# EasyEDA_file_SCH_Meshtastic_ESP32_RA01SH.net
KiCad netlist of a schematic drawn in EasyEDA
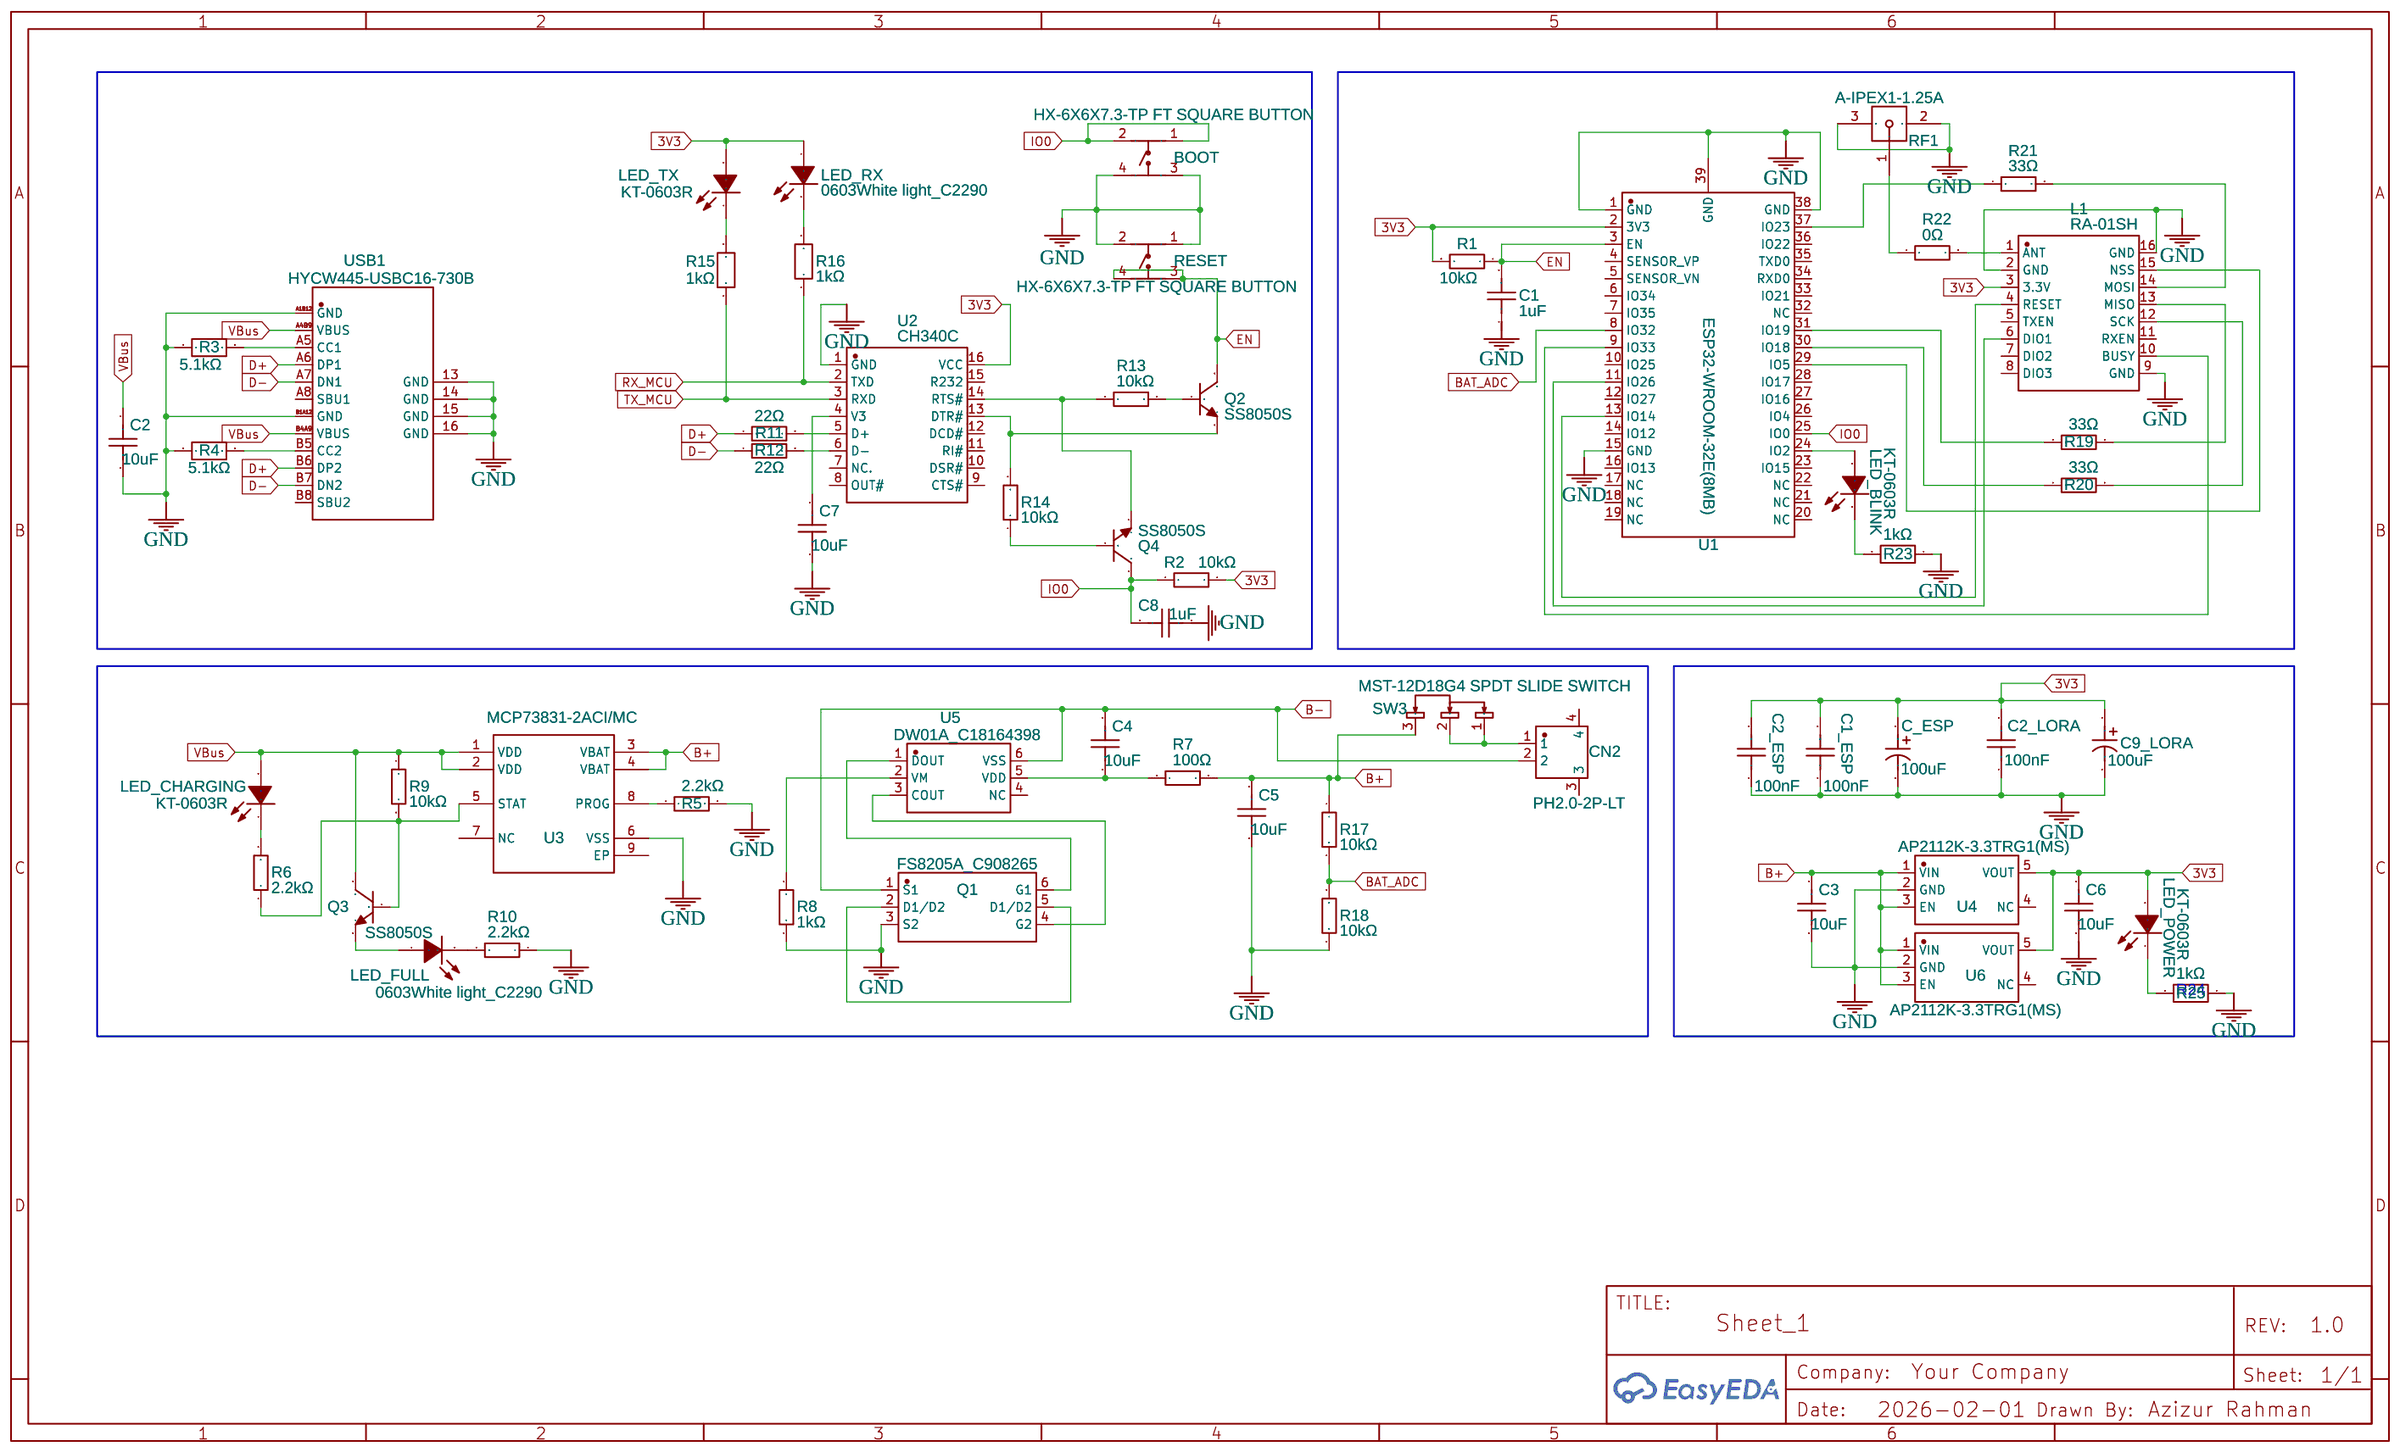
[diagram p0: schematic sheet]

(export (version "E")
  (design (tool "Eeschema 10.0.6"))
  (components
    (comp (ref "BOOT")
      (value "HX-6X6X7.3-TP FT SQUARE BUTTON")
      (fields
        (field (name "Manufacturer Part") "HX-6x6x7.3-TP FT square button")
        (field (name "Manufacturer") "hanxia(韩下)")
      )
      (libsource (lib "") (part "HX-6X6X7.3-TP FT SQUARE BUTTON_1"))
    )
    (comp (ref "C1")
      (value "1uF")
      (fields
        (field (name "Manufacturer Part") "CL10A105KB8NNNC")
        (field (name "Manufacturer") "SAMSUNG(三星)")
      )
      (libsource (lib "") (part "CL10A105KB8NNNC"))
    )
    (comp (ref "C1_ESP")
      (value "100nF")
      (fields
        (field (name "Manufacturer Part") "CL10B104KA8WPNC")
        (field (name "Manufacturer") "SAMSUNG(三星)")
      )
      (libsource (lib "") (part "CL10B104KA8WPNC_2"))
    )
    (comp (ref "C2")
      (value "10uF")
      (fields
        (field (name "Manufacturer Part") "CL10A106KP8NNNC")
        (field (name "Manufacturer") "SAMSUNG(三星)")
      )
      (libsource (lib "") (part "CL10A106KP8NNNC"))
    )
    (comp (ref "C2_ESP")
      (value "100nF")
      (fields
        (field (name "Manufacturer Part") "CL10B104KA8WPNC")
        (field (name "Manufacturer") "SAMSUNG(三星)")
      )
      (libsource (lib "") (part "CL10B104KA8WPNC"))
    )
    (comp (ref "C2_LORA")
      (value "100nF")
      (fields
        (field (name "Manufacturer Part") "CL10B104KA8WPNC")
        (field (name "Manufacturer") "SAMSUNG(三星)")
      )
      (libsource (lib "") (part "CL10B104KA8WPNC_1"))
    )
    (comp (ref "C3")
      (value "10uF")
      (fields
        (field (name "Manufacturer Part") "CL10A106KP8NNNC")
        (field (name "Manufacturer") "SAMSUNG(三星)")
      )
      (libsource (lib "") (part "CL10A106KP8NNNC"))
    )
    (comp (ref "C4")
      (value "10uF")
      (fields
        (field (name "Manufacturer Part") "CL10A106KP8NNNC")
        (field (name "Manufacturer") "SAMSUNG(三星)")
      )
      (libsource (lib "") (part "CL10A106KP8NNNC"))
    )
    (comp (ref "C5")
      (value "10uF")
      (fields
        (field (name "Manufacturer Part") "CL10A106KP8NNNC")
        (field (name "Manufacturer") "SAMSUNG(三星)")
      )
      (libsource (lib "") (part "CL10A106KP8NNNC"))
    )
    (comp (ref "C6")
      (value "10uF")
      (fields
        (field (name "Manufacturer Part") "CL10A106KP8NNNC")
        (field (name "Manufacturer") "SAMSUNG(三星)")
      )
      (libsource (lib "") (part "CL10A106KP8NNNC"))
    )
    (comp (ref "C7")
      (value "10uF")
      (fields
        (field (name "Manufacturer Part") "CL10A106KP8NNNC")
        (field (name "Manufacturer") "SAMSUNG(三星)")
      )
      (libsource (lib "") (part "CL10A106KP8NNNC"))
    )
    (comp (ref "C8")
      (value "1uF")
      (fields
        (field (name "Manufacturer Part") "CL10A105KB8NNNC")
        (field (name "Manufacturer") "SAMSUNG(三星)")
      )
      (libsource (lib "") (part "CL10A105KB8NNNC_1"))
    )
    (comp (ref "C9_LORA")
      (value "100uF")
      (fields
        (field (name "Manufacturer Part") "RVT100UF16V67RV0120")
        (field (name "Manufacturer") "KNSCHA(科尼盛)")
      )
      (libsource (lib "") (part "RVT100UF16V67RV0120_1"))
    )
    (comp (ref "CN2")
      (value "PH2.0-2P-LT")
      (fields (field (name "Manufacturer") "CAX(创都)"))
      (libsource (lib "") (part "PH2.0-2P-LT"))
    )
    (comp (ref "C_ESP")
      (value "100uF")
      (fields
        (field (name "Manufacturer Part") "RVT100UF16V67RV0120")
        (field (name "Manufacturer") "KNSCHA(科尼盛)")
      )
      (libsource (lib "") (part "RVT100UF16V67RV0120"))
    )
    (comp (ref "L1")
      (value "RA-01SH")
      (fields (field (name "Manufacturer Part") "Ra-01SH") (field (name "Manufacturer") "Ai-Thinker(安信可)"))
      (libsource (lib "") (part "RA-01SH"))
    )
    (comp (ref "LED_BLINK")
      (value "KT-0603R")
      (fields (field (name "Manufacturer") "KENTO"))
      (libsource (lib "") (part "KT-0603R_2"))
    )
    (comp (ref "LED_CHARGING")
      (value "KT-0603R")
      (fields (field (name "Manufacturer") "KENTO"))
      (libsource (lib "") (part "KT-0603R_1"))
    )
    (comp (ref "LED_FULL")
      (value "0603White light_C2290")
      (fields (field (name "Manufacturer Part") "KT-0603W") (field (name "Manufacturer") "KENTO"))
      (libsource (lib "") (part "0603White light_C2290_1"))
    )
    (comp (ref "LED_POWER")
      (value "KT-0603R")
      (fields (field (name "Manufacturer") "KENTO"))
      (libsource (lib "") (part "KT-0603R"))
    )
    (comp (ref "LED_RX")
      (value "0603White light_C2290")
      (fields (field (name "Manufacturer Part") "KT-0603W") (field (name "Manufacturer") "KENTO"))
      (libsource (lib "") (part "0603White light_C2290"))
    )
    (comp (ref "LED_TX")
      (value "KT-0603R")
      (fields (field (name "Manufacturer") "KENTO"))
      (libsource (lib "") (part "KT-0603R_3"))
    )
    (comp (ref "Q1")
      (value "FS8205A_C908265")
      (fields (field (name "Manufacturer Part") "FS8205A") (field (name "Manufacturer") "FUXINSEMI(富芯森美)"))
      (libsource (lib "") (part "FS8205A_C908265"))
    )
    (comp (ref "Q2")
      (value "SS8050S")
      (fields (field (name "Manufacturer") "FOSAN(富捷/富信)"))
      (libsource (lib "") (part "SS8050S_2"))
    )
    (comp (ref "Q3")
      (value "SS8050S")
      (fields (field (name "Manufacturer") "FOSAN(富捷/富信)"))
      (libsource (lib "") (part "SS8050S"))
    )
    (comp (ref "Q4")
      (value "SS8050S")
      (fields (field (name "Manufacturer") "FOSAN(富捷/富信)"))
      (libsource (lib "") (part "SS8050S_1"))
    )
    (comp (ref "R1")
      (value "10kΩ")
      (fields
        (field (name "Manufacturer Part") "0603WAF1002T5E")
        (field (name "Manufacturer") "UNI-ROYAL(厚声)")
      )
      (libsource (lib "") (part "0603WAF1002T5E_1"))
    )
    (comp (ref "R2")
      (value "10kΩ")
      (fields
        (field (name "Manufacturer Part") "0603WAF1002T5E")
        (field (name "Manufacturer") "UNI-ROYAL(厚声)")
      )
      (libsource (lib "") (part "0603WAF1002T5E_1"))
    )
    (comp (ref "R3")
      (value "5.1kΩ")
      (fields (field (name "Manufacturer Part") "SCR0603F5K1") (field (name "Manufacturer") "VO(翔胜)"))
      (libsource (lib "") (part "SCR0603F5K1"))
    )
    (comp (ref "R4")
      (value "5.1kΩ")
      (fields (field (name "Manufacturer Part") "SCR0603F5K1") (field (name "Manufacturer") "VO(翔胜)"))
      (libsource (lib "") (part "SCR0603F5K1"))
    )
    (comp (ref "R5")
      (value "2.2kΩ")
      (fields
        (field (name "Manufacturer Part") "0603WAF2201T5E")
        (field (name "Manufacturer") "UNI-ROYAL(厚声)")
      )
      (libsource (lib "") (part "0603WAF2201T5E"))
    )
    (comp (ref "R6")
      (value "2.2kΩ")
      (fields
        (field (name "Manufacturer Part") "0603WAF2201T5E")
        (field (name "Manufacturer") "UNI-ROYAL(厚声)")
      )
      (libsource (lib "") (part "0603WAF2201T5E_2"))
    )
    (comp (ref "R7")
      (value "100Ω")
      (fields
        (field (name "Manufacturer Part") "0603WAF1000T5E")
        (field (name "Manufacturer") "UNI-ROYAL(厚声)")
      )
      (libsource (lib "") (part "0603WAF1000T5E"))
    )
    (comp (ref "R8")
      (value "1kΩ")
      (fields
        (field (name "Manufacturer Part") "0603WAF1001T5E")
        (field (name "Manufacturer") "UNI-ROYAL(厚声)")
      )
      (libsource (lib "") (part "0603WAF1001T5E"))
    )
    (comp (ref "R9")
      (value "10kΩ")
      (fields
        (field (name "Manufacturer Part") "0603WAF1002T5E")
        (field (name "Manufacturer") "UNI-ROYAL(厚声)")
      )
      (libsource (lib "") (part "0603WAF1002T5E"))
    )
    (comp (ref "R10")
      (value "2.2kΩ")
      (fields
        (field (name "Manufacturer Part") "0603WAF2201T5E")
        (field (name "Manufacturer") "UNI-ROYAL(厚声)")
      )
      (libsource (lib "") (part "0603WAF2201T5E_1"))
    )
    (comp (ref "R11")
      (value "22Ω")
      (fields (field (name "Manufacturer Part") "CR1206J40220G") (field (name "Manufacturer") "LIZ(丽智电子)"))
      (libsource (lib "") (part "CR1206J40220G"))
    )
    (comp (ref "R12")
      (value "22Ω")
      (fields (field (name "Manufacturer Part") "CR1206J40220G") (field (name "Manufacturer") "LIZ(丽智电子)"))
      (libsource (lib "") (part "CR1206J40220G"))
    )
    (comp (ref "R13")
      (value "10kΩ")
      (fields
        (field (name "Manufacturer Part") "0603WAF1002T5E")
        (field (name "Manufacturer") "UNI-ROYAL(厚声)")
      )
      (libsource (lib "") (part "0603WAF1002T5E_2"))
    )
    (comp (ref "R14")
      (value "10kΩ")
      (fields
        (field (name "Manufacturer Part") "0603WAF1002T5E")
        (field (name "Manufacturer") "UNI-ROYAL(厚声)")
      )
      (libsource (lib "") (part "0603WAF1002T5E_3"))
    )
    (comp (ref "R15")
      (value "1kΩ")
      (fields (field (name "Manufacturer Part") "FRC1206J102 TS") (field (name "Manufacturer") "FOJAN(富捷)"))
      (libsource (lib "") (part "FRC1206J102 TS_1"))
    )
    (comp (ref "R16")
      (value "1kΩ")
      (fields (field (name "Manufacturer Part") "FRC1206J102 TS") (field (name "Manufacturer") "FOJAN(富捷)"))
      (libsource (lib "") (part "FRC1206J102 TS_1"))
    )
    (comp (ref "R17")
      (value "10kΩ")
      (fields
        (field (name "Manufacturer Part") "0603WAF1002T5E")
        (field (name "Manufacturer") "UNI-ROYAL(厚声)")
      )
      (libsource (lib "") (part "0603WAF1002T5E"))
    )
    (comp (ref "R18")
      (value "10kΩ")
      (fields
        (field (name "Manufacturer Part") "0603WAF1002T5E")
        (field (name "Manufacturer") "UNI-ROYAL(厚声)")
      )
      (libsource (lib "") (part "0603WAF1002T5E"))
    )
    (comp (ref "R19")
      (value "33Ω")
      (fields
        (field (name "Manufacturer Part") "0603WAF330JT5E")
        (field (name "Manufacturer") "UNI-ROYAL(厚声)")
      )
      (libsource (lib "") (part "0603WAF330JT5E"))
    )
    (comp (ref "R20")
      (value "33Ω")
      (fields
        (field (name "Manufacturer Part") "0603WAF330JT5E")
        (field (name "Manufacturer") "UNI-ROYAL(厚声)")
      )
      (libsource (lib "") (part "0603WAF330JT5E"))
    )
    (comp (ref "R21")
      (value "33Ω")
      (fields
        (field (name "Manufacturer Part") "0603WAF330JT5E")
        (field (name "Manufacturer") "UNI-ROYAL(厚声)")
      )
      (libsource (lib "") (part "0603WAF330JT5E"))
    )
    (comp (ref "R22")
      (value "0Ω")
      (fields
        (field (name "Manufacturer Part") "0805W8J0000T5E")
        (field (name "Manufacturer") "UNI-ROYAL(厚声)")
      )
      (libsource (lib "") (part "0805W8J0000T5E"))
    )
    (comp (ref "R23")
      (value "1kΩ")
      (fields (field (name "Manufacturer Part") "FRC1206J102 TS") (field (name "Manufacturer") "FOJAN(富捷)"))
      (libsource (lib "") (part "FRC1206J102 TS"))
    )
    (comp (ref "R25")
      (value "1kΩ")
      (fields (field (name "Manufacturer Part") "FRC1206J102 TS") (field (name "Manufacturer") "FOJAN(富捷)"))
      (libsource (lib "") (part "FRC1206J102 TS"))
    )
    (comp (ref "RESET")
      (value "HX-6X6X7.3-TP FT SQUARE BUTTON")
      (fields
        (field (name "Manufacturer Part") "HX-6x6x7.3-TP FT square button")
        (field (name "Manufacturer") "hanxia(韩下)")
      )
      (libsource (lib "") (part "HX-6X6X7.3-TP FT SQUARE BUTTON"))
    )
    (comp (ref "RF1")
      (value "A-IPEX1-1.25A")
      (fields (field (name "Manufacturer") "MyAntenna(摩天射频)"))
      (libsource (lib "") (part "A-IPEX1-1.25A"))
    )
    (comp (ref "SW3")
      (value "MST-12D18G4 SPDT SLIDE SWITCH")
      (fields
        (field (name "Manufacturer Part") "MST-12D18G4 SPDT Slide Switch")
        (field (name "Manufacturer") "SHOU HAN(首韩)")
      )
      (libsource (lib "") (part "MST-12D18G4 SPDT SLIDE SWITCH"))
    )
    (comp (ref "U1")
      (value "ESP32-WROOM-32E(8MB)")
      (fields
        (field (name "Manufacturer Part") "ESP32-WROOM-32E-N8")
        (field (name "Manufacturer") "ESPRESSIF(乐鑫)")
      )
      (libsource (lib "") (part "ESP32-WROOM-32E(8MB)"))
    )
    (comp (ref "U2")
      (value "CH340C")
      (fields (field (name "Manufacturer") "WCH(南京沁恒)"))
      (libsource (lib "") (part "CH340C"))
    )
    (comp (ref "U3")
      (value "MCP73831-2ACI/MC")
      (fields (field (name "Manufacturer") "MICROCHIP(美国微芯)"))
      (libsource (lib "") (part "MCP73831-2ACI/MC"))
    )
    (comp (ref "U4")
      (value "AP2112K-3.3TRG1(MS)")
      (fields (field (name "Manufacturer") "MSKSEMI(美森科)"))
      (libsource (lib "") (part "AP2112K-3.3TRG1(MS)"))
    )
    (comp (ref "U5")
      (value "DW01A_C18164398")
      (fields (field (name "Manufacturer Part") "DW01A") (field (name "Manufacturer") "HL(富海微)"))
      (libsource (lib "") (part "DW01A_C18164398"))
    )
    (comp (ref "U6")
      (value "AP2112K-3.3TRG1(MS)")
      (fields (field (name "Manufacturer") "MSKSEMI(美森科)"))
      (libsource (lib "") (part "AP2112K-3.3TRG1(MS)"))
    )
    (comp (ref "USB1")
      (value "HYCW445-USBC16-730B")
      (fields (field (name "Manufacturer") "华宇创"))
      (libsource (lib "") (part "HYCW445-USBC16-730B"))
    )
  )
  (nets
    (net (code "1") (name "3V3") (class "Default")
      (node (ref "C1_ESP") (pin "2") (pinfunction "2_2") (pintype "unspecified"))
      (node (ref "C2_ESP") (pin "2") (pinfunction "2_2") (pintype "unspecified"))
      (node (ref "C2_LORA") (pin "2") (pinfunction "2_2") (pintype "unspecified"))
      (node (ref "C6") (pin "1") (pinfunction "1_1") (pintype "unspecified"))
      (node (ref "C9_LORA") (pin "1") (pinfunction "1_1") (pintype "input"))
      (node (ref "C_ESP") (pin "1") (pinfunction "1_1") (pintype "input"))
      (node (ref "L1") (pin "3") (pinfunction "3.3V_3") (pintype "unspecified"))
      (node (ref "LED_POWER") (pin "2") (pinfunction "A_2") (pintype "unspecified"))
      (node (ref "LED_RX") (pin "1") (pinfunction "A_1") (pintype "unspecified"))
      (node (ref "LED_TX") (pin "2") (pinfunction "A_2") (pintype "unspecified"))
      (node (ref "R1") (pin "2") (pinfunction "2_2") (pintype "input"))
      (node (ref "R2") (pin "1") (pinfunction "1_1") (pintype "input"))
      (node (ref "U1") (pin "2") (pinfunction "3V3_2") (pintype "unspecified"))
      (node (ref "U2") (pin "16") (pinfunction "VCC_16") (pintype "unspecified"))
      (node (ref "U4") (pin "5") (pinfunction "VOUT_5") (pintype "unspecified"))
      (node (ref "U6") (pin "5") (pinfunction "VOUT_5") (pintype "unspecified"))
    )
    (net (code "2") (name "B+") (class "Default")
      (node (ref "C3") (pin "1") (pinfunction "1_1") (pintype "unspecified"))
      (node (ref "C5") (pin "1") (pinfunction "1_1") (pintype "unspecified"))
      (node (ref "R17") (pin "1") (pinfunction "1_1") (pintype "input"))
      (node (ref "R7") (pin "2") (pinfunction "2_2") (pintype "input"))
      (node (ref "SW3") (pin "3") (pinfunction "3_3") (pintype "unspecified"))
      (node (ref "U3") (pin "3") (pinfunction "VBAT_3") (pintype "passive"))
      (node (ref "U3") (pin "4") (pinfunction "VBAT_4") (pintype "passive"))
      (node (ref "U4") (pin "1") (pinfunction "VIN_1") (pintype "unspecified"))
      (node (ref "U4") (pin "3") (pinfunction "EN_3") (pintype "unspecified"))
      (node (ref "U6") (pin "1") (pinfunction "VIN_1") (pintype "unspecified"))
      (node (ref "U6") (pin "3") (pinfunction "EN_3") (pintype "unspecified"))
    )
    (net (code "3") (name "B-") (class "Default")
      (node (ref "C4") (pin "1") (pinfunction "1_1") (pintype "unspecified"))
      (node (ref "CN2") (pin "2") (pinfunction "2_2") (pintype "unspecified"))
      (node (ref "Q1") (pin "1") (pinfunction "S1_1") (pintype "unspecified"))
      (node (ref "U5") (pin "6") (pinfunction "VSS_6") (pintype "unspecified"))
    )
    (net (code "4") (name "BAT_ADC") (class "Default")
      (node (ref "R17") (pin "2") (pinfunction "2_2") (pintype "input"))
      (node (ref "R18") (pin "1") (pinfunction "1_1") (pintype "input"))
      (node (ref "U1") (pin "8") (pinfunction "IO32_8") (pintype "unspecified"))
    )
    (net (code "5") (name "D+") (class "Default")
      (node (ref "R11") (pin "1") (pinfunction "1_1") (pintype "input"))
      (node (ref "USB1") (pin "A6") (pinfunction "DP1_A6") (pintype "unspecified"))
      (node (ref "USB1") (pin "B6") (pinfunction "DP2_B6") (pintype "unspecified"))
    )
    (net (code "6") (name "D-") (class "Default")
      (node (ref "R12") (pin "1") (pinfunction "1_1") (pintype "input"))
      (node (ref "USB1") (pin "A7") (pinfunction "DN1_A7") (pintype "unspecified"))
      (node (ref "USB1") (pin "B7") (pinfunction "DN2_B7") (pintype "unspecified"))
    )
    (net (code "7") (name "EN") (class "Default")
      (node (ref "C1") (pin "2") (pinfunction "2_2") (pintype "unspecified"))
      (node (ref "Q2") (pin "3") (pinfunction "C_3") (pintype "input"))
      (node (ref "R1") (pin "1") (pinfunction "1_1") (pintype "input"))
      (node (ref "RESET") (pin "3") (pinfunction "C_3") (pintype "unspecified"))
      (node (ref "RESET") (pin "4") (pinfunction "D_4") (pintype "unspecified"))
      (node (ref "U1") (pin "3") (pinfunction "EN_3") (pintype "unspecified"))
    )
    (net (code "8") (name "GND") (class "Default")
      (node (ref "BOOT") (pin "3") (pinfunction "C_3") (pintype "unspecified"))
      (node (ref "BOOT") (pin "4") (pinfunction "D_4") (pintype "unspecified"))
      (node (ref "C1") (pin "1") (pinfunction "1_1") (pintype "unspecified"))
      (node (ref "C1_ESP") (pin "1") (pinfunction "1_1") (pintype "unspecified"))
      (node (ref "C2") (pin "2") (pinfunction "2_2") (pintype "unspecified"))
      (node (ref "C2_ESP") (pin "1") (pinfunction "1_1") (pintype "unspecified"))
      (node (ref "C2_LORA") (pin "1") (pinfunction "1_1") (pintype "unspecified"))
      (node (ref "C3") (pin "2") (pinfunction "2_2") (pintype "unspecified"))
      (node (ref "C5") (pin "2") (pinfunction "2_2") (pintype "unspecified"))
      (node (ref "C6") (pin "2") (pinfunction "2_2") (pintype "unspecified"))
      (node (ref "C7") (pin "2") (pinfunction "2_2") (pintype "unspecified"))
      (node (ref "C8") (pin "1") (pinfunction "1_1") (pintype "unspecified"))
      (node (ref "C9_LORA") (pin "2") (pinfunction "2_2") (pintype "input"))
      (node (ref "C_ESP") (pin "2") (pinfunction "2_2") (pintype "input"))
      (node (ref "L1") (pin "16") (pinfunction "GND_16") (pintype "unspecified"))
      (node (ref "L1") (pin "2") (pinfunction "GND_2") (pintype "unspecified"))
      (node (ref "L1") (pin "9") (pinfunction "GND_9") (pintype "unspecified"))
      (node (ref "Q1") (pin "3") (pinfunction "S2_3") (pintype "unspecified"))
      (node (ref "R10") (pin "1") (pinfunction "1_1") (pintype "input"))
      (node (ref "R18") (pin "2") (pinfunction "2_2") (pintype "input"))
      (node (ref "R23") (pin "1") (pinfunction "1_1") (pintype "unspecified"))
      (node (ref "R25") (pin "1") (pinfunction "1_1") (pintype "unspecified"))
      (node (ref "R3") (pin "1") (pinfunction "1_1") (pintype "unspecified"))
      (node (ref "R4") (pin "1") (pinfunction "1_1") (pintype "unspecified"))
      (node (ref "R5") (pin "2") (pinfunction "2_2") (pintype "input"))
      (node (ref "R8") (pin "2") (pinfunction "2_2") (pintype "input"))
      (node (ref "RESET") (pin "1") (pinfunction "A_1") (pintype "unspecified"))
      (node (ref "RESET") (pin "2") (pinfunction "B_2") (pintype "unspecified"))
      (node (ref "RF1") (pin "2") (pinfunction "2_2") (pintype "unspecified"))
      (node (ref "RF1") (pin "3") (pinfunction "3_3") (pintype "unspecified"))
      (node (ref "U1") (pin "1") (pinfunction "GND_1") (pintype "unspecified"))
      (node (ref "U1") (pin "15") (pinfunction "GND_15") (pintype "unspecified"))
      (node (ref "U1") (pin "38") (pinfunction "GND_38") (pintype "unspecified"))
      (node (ref "U1") (pin "39") (pinfunction "GND_39") (pintype "unspecified"))
      (node (ref "U2") (pin "1") (pinfunction "GND_1") (pintype "unspecified"))
      (node (ref "U3") (pin "6") (pinfunction "VSS_6") (pintype "passive"))
      (node (ref "U4") (pin "2") (pinfunction "GND_2") (pintype "unspecified"))
      (node (ref "U6") (pin "2") (pinfunction "GND_2") (pintype "unspecified"))
      (node (ref "USB1") (pin "13") (pinfunction "GND_13") (pintype "unspecified"))
      (node (ref "USB1") (pin "14") (pinfunction "GND_14") (pintype "unspecified"))
      (node (ref "USB1") (pin "15") (pinfunction "GND_15") (pintype "unspecified"))
      (node (ref "USB1") (pin "16") (pinfunction "GND_16") (pintype "unspecified"))
      (node (ref "USB1") (pin "A1B12") (pinfunction "GND_A1B12") (pintype "unspecified"))
      (node (ref "USB1") (pin "B1A12") (pinfunction "GND_B1A12") (pintype "unspecified"))
    )
    (net (code "9") (name "IO0") (class "Default")
      (node (ref "BOOT") (pin "1") (pinfunction "A_1") (pintype "unspecified"))
      (node (ref "BOOT") (pin "2") (pinfunction "B_2") (pintype "unspecified"))
      (node (ref "C8") (pin "2") (pinfunction "2_2") (pintype "unspecified"))
      (node (ref "Q4") (pin "3") (pinfunction "C_3") (pintype "input"))
      (node (ref "R2") (pin "2") (pinfunction "2_2") (pintype "input"))
      (node (ref "U1") (pin "25") (pinfunction "IO0_25") (pintype "unspecified"))
    )
    (net (code "10") (name "Net-(CN2-Pad1)") (class "Default")
      (node (ref "CN2") (pin "1") (pinfunction "1_1") (pintype "unspecified"))
      (node (ref "SW3") (pin "1") (pinfunction "1_1") (pintype "unspecified"))
      (node (ref "SW3") (pin "2") (pinfunction "2_2") (pintype "unspecified"))
    )
    (net (code "11") (name "Net-(L1-ANT)") (class "Default")
      (node (ref "L1") (pin "1") (pinfunction "ANT_1") (pintype "unspecified"))
      (node (ref "R22") (pin "2") (pinfunction "2_2") (pintype "input"))
    )
    (net (code "12") (name "Net-(L1-BUSY)") (class "Default")
      (node (ref "L1") (pin "10") (pinfunction "BUSY_10") (pintype "unspecified"))
      (node (ref "U1") (pin "9") (pinfunction "IO33_9") (pintype "unspecified"))
    )
    (net (code "13") (name "Net-(L1-DIO1)") (class "Default")
      (node (ref "L1") (pin "6") (pinfunction "DIO1_6") (pintype "unspecified"))
      (node (ref "U1") (pin "11") (pinfunction "IO26_11") (pintype "unspecified"))
    )
    (net (code "14") (name "Net-(L1-MISO)") (class "Default")
      (node (ref "L1") (pin "13") (pinfunction "MISO_13") (pintype "unspecified"))
      (node (ref "R19") (pin "2") (pinfunction "2_2") (pintype "input"))
    )
    (net (code "15") (name "Net-(L1-MOSI)") (class "Default")
      (node (ref "L1") (pin "14") (pinfunction "MOSI_14") (pintype "unspecified"))
      (node (ref "R21") (pin "2") (pinfunction "2_2") (pintype "input"))
    )
    (net (code "16") (name "Net-(L1-NSS)") (class "Default")
      (node (ref "L1") (pin "15") (pinfunction "NSS_15") (pintype "unspecified"))
      (node (ref "U1") (pin "29") (pinfunction "IO5_29") (pintype "unspecified"))
    )
    (net (code "17") (name "Net-(L1-RESET)") (class "Default")
      (node (ref "L1") (pin "4") (pinfunction "RESET_4") (pintype "unspecified"))
      (node (ref "U1") (pin "13") (pinfunction "IO14_13") (pintype "unspecified"))
    )
    (net (code "18") (name "Net-(L1-SCK)") (class "Default")
      (node (ref "L1") (pin "12") (pinfunction "SCK_12") (pintype "unspecified"))
      (node (ref "R20") (pin "2") (pinfunction "2_2") (pintype "input"))
    )
    (net (code "19") (name "Net-(LED_BLINK-A)") (class "Default")
      (node (ref "LED_BLINK") (pin "2") (pinfunction "A_2") (pintype "unspecified"))
      (node (ref "U1") (pin "24") (pinfunction "IO2_24") (pintype "unspecified"))
    )
    (net (code "20") (name "Net-(LED_BLINK-K)") (class "Default")
      (node (ref "LED_BLINK") (pin "1") (pinfunction "K_1") (pintype "unspecified"))
      (node (ref "R23") (pin "2") (pinfunction "2_2") (pintype "unspecified"))
    )
    (net (code "21") (name "Net-(LED_CHARGING-K)") (class "Default")
      (node (ref "LED_CHARGING") (pin "1") (pinfunction "K_1") (pintype "unspecified"))
      (node (ref "R6") (pin "2") (pinfunction "2_2") (pintype "input"))
    )
    (net (code "22") (name "Net-(LED_FULL-A)") (class "Default")
      (node (ref "LED_FULL") (pin "1") (pinfunction "A_1") (pintype "unspecified"))
      (node (ref "Q3") (pin "2") (pinfunction "E_2") (pintype "input"))
    )
    (net (code "23") (name "Net-(LED_FULL-K)") (class "Default")
      (node (ref "LED_FULL") (pin "2") (pinfunction "K_2") (pintype "unspecified"))
      (node (ref "R10") (pin "2") (pinfunction "2_2") (pintype "input"))
    )
    (net (code "24") (name "Net-(LED_POWER-K)") (class "Default")
      (node (ref "LED_POWER") (pin "1") (pinfunction "K_1") (pintype "unspecified"))
      (node (ref "R25") (pin "2") (pinfunction "2_2") (pintype "unspecified"))
    )
    (net (code "25") (name "Net-(LED_RX-K)") (class "Default")
      (node (ref "LED_RX") (pin "2") (pinfunction "K_2") (pintype "unspecified"))
      (node (ref "R16") (pin "2") (pinfunction "2_2") (pintype "unspecified"))
    )
    (net (code "26") (name "Net-(LED_TX-K)") (class "Default")
      (node (ref "LED_TX") (pin "1") (pinfunction "K_1") (pintype "unspecified"))
      (node (ref "R15") (pin "2") (pinfunction "2_2") (pintype "unspecified"))
    )
    (net (code "27") (name "Net-(Q1-D1{slash}D2-Pad2)") (class "Default")
      (node (ref "Q1") (pin "2") (pinfunction "D1/D2_2") (pintype "unspecified"))
      (node (ref "Q1") (pin "5") (pinfunction "D1/D2_5") (pintype "unspecified"))
    )
    (net (code "28") (name "Net-(Q1-G1)") (class "Default")
      (node (ref "Q1") (pin "6") (pinfunction "G1_6") (pintype "unspecified"))
      (node (ref "U5") (pin "1") (pinfunction "DOUT_1") (pintype "unspecified"))
    )
    (net (code "29") (name "Net-(Q1-G2)") (class "Default")
      (node (ref "Q1") (pin "4") (pinfunction "G2_4") (pintype "unspecified"))
      (node (ref "U5") (pin "3") (pinfunction "COUT_3") (pintype "unspecified"))
    )
    (net (code "30") (name "Net-(Q2-B)") (class "Default")
      (node (ref "Q2") (pin "1") (pinfunction "B_1") (pintype "input"))
      (node (ref "R13") (pin "2") (pinfunction "2_2") (pintype "input"))
    )
    (net (code "31") (name "Net-(Q2-E)") (class "Default")
      (node (ref "Q2") (pin "2") (pinfunction "E_2") (pintype "input"))
      (node (ref "R14") (pin "2") (pinfunction "2_2") (pintype "input"))
      (node (ref "U2") (pin "13") (pinfunction "DTR#_13") (pintype "unspecified"))
    )
    (net (code "32") (name "Net-(Q3-B)") (class "Default")
      (node (ref "Q3") (pin "1") (pinfunction "B_1") (pintype "input"))
      (node (ref "R6") (pin "1") (pinfunction "1_1") (pintype "input"))
      (node (ref "R9") (pin "2") (pinfunction "2_2") (pintype "input"))
      (node (ref "U3") (pin "5") (pinfunction "STAT_5") (pintype "output"))
    )
    (net (code "33") (name "Net-(Q4-B)") (class "Default")
      (node (ref "Q4") (pin "1") (pinfunction "B_1") (pintype "input"))
      (node (ref "R14") (pin "1") (pinfunction "1_1") (pintype "input"))
    )
    (net (code "34") (name "Net-(Q4-E)") (class "Default")
      (node (ref "Q4") (pin "2") (pinfunction "E_2") (pintype "input"))
      (node (ref "R13") (pin "1") (pinfunction "1_1") (pintype "input"))
      (node (ref "U2") (pin "14") (pinfunction "RTS#_14") (pintype "unspecified"))
    )
    (net (code "35") (name "Net-(R22-Pad1)") (class "Default")
      (node (ref "R22") (pin "1") (pinfunction "1_1") (pintype "input"))
      (node (ref "RF1") (pin "1") (pinfunction "1_1") (pintype "unspecified"))
    )
    (net (code "36") (name "Net-(U1-IO18)") (class "Default")
      (node (ref "R20") (pin "1") (pinfunction "1_1") (pintype "input"))
      (node (ref "U1") (pin "30") (pinfunction "IO18_30") (pintype "unspecified"))
    )
    (net (code "37") (name "Net-(U1-IO19)") (class "Default")
      (node (ref "R19") (pin "1") (pinfunction "1_1") (pintype "input"))
      (node (ref "U1") (pin "31") (pinfunction "IO19_31") (pintype "unspecified"))
    )
    (net (code "38") (name "Net-(U1-IO23)") (class "Default")
      (node (ref "R21") (pin "1") (pinfunction "1_1") (pintype "input"))
      (node (ref "U1") (pin "37") (pinfunction "IO23_37") (pintype "unspecified"))
    )
    (net (code "39") (name "Net-(U2-D+)") (class "Default")
      (node (ref "R11") (pin "2") (pinfunction "2_2") (pintype "input"))
      (node (ref "U2") (pin "5") (pinfunction "D+_5") (pintype "unspecified"))
    )
    (net (code "40") (name "Net-(U2-D-)") (class "Default")
      (node (ref "R12") (pin "2") (pinfunction "2_2") (pintype "input"))
      (node (ref "U2") (pin "6") (pinfunction "D-_6") (pintype "unspecified"))
    )
    (net (code "41") (name "Net-(U2-V3)") (class "Default")
      (node (ref "C7") (pin "1") (pinfunction "1_1") (pintype "unspecified"))
      (node (ref "U2") (pin "4") (pinfunction "V3_4") (pintype "unspecified"))
    )
    (net (code "42") (name "Net-(U3-PROG)") (class "Default")
      (node (ref "R5") (pin "1") (pinfunction "1_1") (pintype "input"))
      (node (ref "U3") (pin "8") (pinfunction "PROG_8") (pintype "unspecified"))
    )
    (net (code "43") (name "Net-(U5-VDD)") (class "Default")
      (node (ref "C4") (pin "2") (pinfunction "2_2") (pintype "unspecified"))
      (node (ref "R7") (pin "1") (pinfunction "1_1") (pintype "input"))
      (node (ref "U5") (pin "5") (pinfunction "VDD_5") (pintype "unspecified"))
    )
    (net (code "44") (name "Net-(U5-VM)") (class "Default")
      (node (ref "R8") (pin "1") (pinfunction "1_1") (pintype "input"))
      (node (ref "U5") (pin "2") (pinfunction "VM_2") (pintype "unspecified"))
    )
    (net (code "45") (name "Net-(USB1-CC1)") (class "Default")
      (node (ref "R3") (pin "2") (pinfunction "2_2") (pintype "unspecified"))
      (node (ref "USB1") (pin "A5") (pinfunction "CC1_A5") (pintype "unspecified"))
    )
    (net (code "46") (name "Net-(USB1-CC2)") (class "Default")
      (node (ref "R4") (pin "2") (pinfunction "2_2") (pintype "unspecified"))
      (node (ref "USB1") (pin "B5") (pinfunction "CC2_B5") (pintype "unspecified"))
    )
    (net (code "47") (name "RX_MCU") (class "Default")
      (node (ref "R16") (pin "1") (pinfunction "1_1") (pintype "unspecified"))
      (node (ref "U2") (pin "2") (pinfunction "TXD_2") (pintype "unspecified"))
    )
    (net (code "48") (name "TX_MCU") (class "Default")
      (node (ref "R15") (pin "1") (pinfunction "1_1") (pintype "unspecified"))
      (node (ref "U2") (pin "3") (pinfunction "RXD_3") (pintype "unspecified"))
    )
    (net (code "49") (name "VBus") (class "Default")
      (node (ref "C2") (pin "1") (pinfunction "1_1") (pintype "unspecified"))
      (node (ref "LED_CHARGING") (pin "2") (pinfunction "A_2") (pintype "unspecified"))
      (node (ref "Q3") (pin "3") (pinfunction "C_3") (pintype "input"))
      (node (ref "R9") (pin "1") (pinfunction "1_1") (pintype "input"))
      (node (ref "U3") (pin "1") (pinfunction "VDD_1") (pintype "passive"))
      (node (ref "U3") (pin "2") (pinfunction "VDD_2") (pintype "passive"))
      (node (ref "USB1") (pin "A4B9") (pinfunction "VBUS_A4B9") (pintype "unspecified"))
      (node (ref "USB1") (pin "B4A9") (pinfunction "VBUS_B4A9") (pintype "unspecified"))
    )
    (net (code "50") (name "unconnected-(CN2-Pad3)") (class "Default")
      (node (ref "CN2") (pin "3") (pinfunction "3_3") (pintype "unspecified"))
    )
    (net (code "51") (name "unconnected-(CN2-Pad4)") (class "Default")
      (node (ref "CN2") (pin "4") (pinfunction "4_4") (pintype "unspecified"))
    )
    (net (code "52") (name "unconnected-(L1-DIO2-Pad7)") (class "Default")
      (node (ref "L1") (pin "7") (pinfunction "DIO2_7") (pintype "unspecified"))
    )
    (net (code "53") (name "unconnected-(L1-DIO3-Pad8)") (class "Default")
      (node (ref "L1") (pin "8") (pinfunction "DIO3_8") (pintype "unspecified"))
    )
    (net (code "54") (name "unconnected-(L1-RXEN-Pad11)") (class "Default")
      (node (ref "L1") (pin "11") (pinfunction "RXEN_11") (pintype "unspecified"))
    )
    (net (code "55") (name "unconnected-(L1-TXEN-Pad5)") (class "Default")
      (node (ref "L1") (pin "5") (pinfunction "TXEN_5") (pintype "unspecified"))
    )
    (net (code "56") (name "unconnected-(U1-IO4-Pad26)") (class "Default")
      (node (ref "U1") (pin "26") (pinfunction "IO4_26") (pintype "unspecified"))
    )
    (net (code "57") (name "unconnected-(U1-IO12-Pad14)") (class "Default")
      (node (ref "U1") (pin "14") (pinfunction "IO12_14") (pintype "unspecified"))
    )
    (net (code "58") (name "unconnected-(U1-IO13-Pad16)") (class "Default")
      (node (ref "U1") (pin "16") (pinfunction "IO13_16") (pintype "unspecified"))
    )
    (net (code "59") (name "unconnected-(U1-IO15-Pad23)") (class "Default")
      (node (ref "U1") (pin "23") (pinfunction "IO15_23") (pintype "unspecified"))
    )
    (net (code "60") (name "unconnected-(U1-IO16-Pad27)") (class "Default")
      (node (ref "U1") (pin "27") (pinfunction "IO16_27") (pintype "unspecified"))
    )
    (net (code "61") (name "unconnected-(U1-IO17-Pad28)") (class "Default")
      (node (ref "U1") (pin "28") (pinfunction "IO17_28") (pintype "unspecified"))
    )
    (net (code "62") (name "unconnected-(U1-IO21-Pad33)") (class "Default")
      (node (ref "U1") (pin "33") (pinfunction "IO21_33") (pintype "unspecified"))
    )
    (net (code "63") (name "unconnected-(U1-IO22-Pad36)") (class "Default")
      (node (ref "U1") (pin "36") (pinfunction "IO22_36") (pintype "unspecified"))
    )
    (net (code "64") (name "unconnected-(U1-IO25-Pad10)") (class "Default")
      (node (ref "U1") (pin "10") (pinfunction "IO25_10") (pintype "unspecified"))
    )
    (net (code "65") (name "unconnected-(U1-IO27-Pad12)") (class "Default")
      (node (ref "U1") (pin "12") (pinfunction "IO27_12") (pintype "unspecified"))
    )
    (net (code "66") (name "unconnected-(U1-IO34-Pad6)") (class "Default")
      (node (ref "U1") (pin "6") (pinfunction "IO34_6") (pintype "unspecified"))
    )
    (net (code "67") (name "unconnected-(U1-IO35-Pad7)") (class "Default")
      (node (ref "U1") (pin "7") (pinfunction "IO35_7") (pintype "unspecified"))
    )
    (net (code "68") (name "unconnected-(U1-NC-Pad17)") (class "Default")
      (node (ref "U1") (pin "17") (pinfunction "NC_17") (pintype "unspecified"))
    )
    (net (code "69") (name "unconnected-(U1-NC-Pad18)") (class "Default")
      (node (ref "U1") (pin "18") (pinfunction "NC_18") (pintype "unspecified"))
    )
    (net (code "70") (name "unconnected-(U1-NC-Pad19)") (class "Default")
      (node (ref "U1") (pin "19") (pinfunction "NC_19") (pintype "unspecified"))
    )
    (net (code "71") (name "unconnected-(U1-NC-Pad20)") (class "Default")
      (node (ref "U1") (pin "20") (pinfunction "NC_20") (pintype "unspecified"))
    )
    (net (code "72") (name "unconnected-(U1-NC-Pad21)") (class "Default")
      (node (ref "U1") (pin "21") (pinfunction "NC_21") (pintype "unspecified"))
    )
    (net (code "73") (name "unconnected-(U1-NC-Pad22)") (class "Default")
      (node (ref "U1") (pin "22") (pinfunction "NC_22") (pintype "unspecified"))
    )
    (net (code "74") (name "unconnected-(U1-NC-Pad32)") (class "Default")
      (node (ref "U1") (pin "32") (pinfunction "NC_32") (pintype "unspecified"))
    )
    (net (code "75") (name "unconnected-(U1-RXD0-Pad34)") (class "Default")
      (node (ref "U1") (pin "34") (pinfunction "RXD0_34") (pintype "unspecified"))
    )
    (net (code "76") (name "unconnected-(U1-SENSOR_VN-Pad5)") (class "Default")
      (node (ref "U1") (pin "5") (pinfunction "SENSOR_VN_5") (pintype "unspecified"))
    )
    (net (code "77") (name "unconnected-(U1-SENSOR_VP-Pad4)") (class "Default")
      (node (ref "U1") (pin "4") (pinfunction "SENSOR_VP_4") (pintype "unspecified"))
    )
    (net (code "78") (name "unconnected-(U1-TXD0-Pad35)") (class "Default")
      (node (ref "U1") (pin "35") (pinfunction "TXD0_35") (pintype "unspecified"))
    )
    (net (code "79") (name "unconnected-(U2-CTS#-Pad9)") (class "Default")
      (node (ref "U2") (pin "9") (pinfunction "CTS#_9") (pintype "unspecified"))
    )
    (net (code "80") (name "unconnected-(U2-DCD#-Pad12)") (class "Default")
      (node (ref "U2") (pin "12") (pinfunction "DCD#_12") (pintype "unspecified"))
    )
    (net (code "81") (name "unconnected-(U2-DSR#-Pad10)") (class "Default")
      (node (ref "U2") (pin "10") (pinfunction "DSR#_10") (pintype "unspecified"))
    )
    (net (code "82") (name "unconnected-(U2-NC.-Pad7)") (class "Default")
      (node (ref "U2") (pin "7") (pinfunction "NC._7") (pintype "unspecified"))
    )
    (net (code "83") (name "unconnected-(U2-OUT#-Pad8)") (class "Default")
      (node (ref "U2") (pin "8") (pinfunction "OUT#_8") (pintype "unspecified"))
    )
    (net (code "84") (name "unconnected-(U2-R232-Pad15)") (class "Default")
      (node (ref "U2") (pin "15") (pinfunction "R232_15") (pintype "unspecified"))
    )
    (net (code "85") (name "unconnected-(U2-RI#-Pad11)") (class "Default")
      (node (ref "U2") (pin "11") (pinfunction "RI#_11") (pintype "unspecified"))
    )
    (net (code "86") (name "unconnected-(U3-EP-Pad9)") (class "Default")
      (node (ref "U3") (pin "9") (pinfunction "EP_9") (pintype "passive"))
    )
    (net (code "87") (name "unconnected-(U3-NC-Pad7)") (class "Default")
      (node (ref "U3") (pin "7") (pinfunction "NC_7") (pintype "unspecified"))
    )
    (net (code "88") (name "unconnected-(U4-NC-Pad4)") (class "Default")
      (node (ref "U4") (pin "4") (pinfunction "NC_4") (pintype "unspecified"))
    )
    (net (code "89") (name "unconnected-(U5-NC-Pad4)") (class "Default")
      (node (ref "U5") (pin "4") (pinfunction "NC_4") (pintype "unspecified"))
    )
    (net (code "90") (name "unconnected-(U6-NC-Pad4)") (class "Default")
      (node (ref "U6") (pin "4") (pinfunction "NC_4") (pintype "unspecified"))
    )
    (net (code "91") (name "unconnected-(USB1-SBU1-PadA8)") (class "Default")
      (node (ref "USB1") (pin "A8") (pinfunction "SBU1_A8") (pintype "unspecified"))
    )
    (net (code "92") (name "unconnected-(USB1-SBU2-PadB8)") (class "Default")
      (node (ref "USB1") (pin "B8") (pinfunction "SBU2_B8") (pintype "unspecified"))
    )
  )
)
